# brakelight_V3.net
KiCad netlist of a schematic drawn in EAGLE
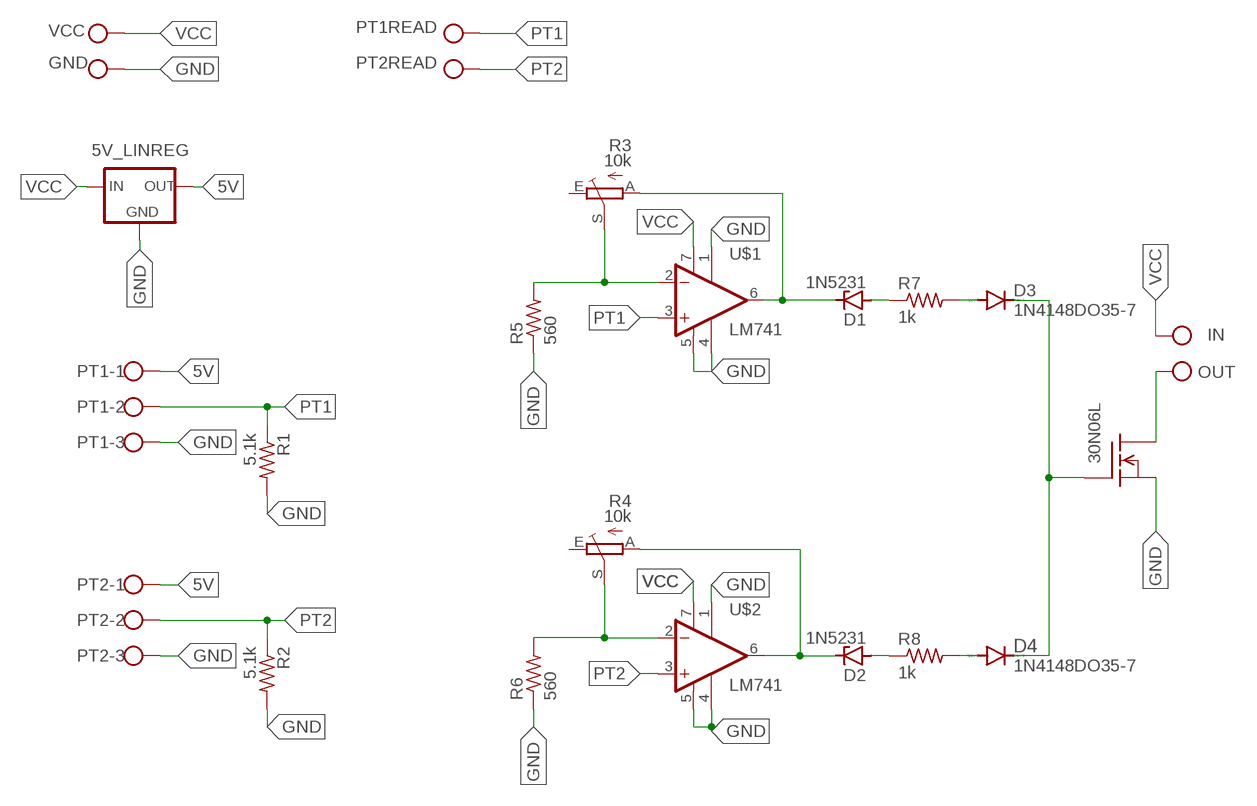
[diagram p0: schematic, sheet 1]

(export (version "E")
  (design (tool "Eeschema 10.0.6"))
  (components
    (comp (ref "5V_LINREG")
      (value "78XXL")
      (footprint "eagle-import:78XXL")
      (libsource (lib "eagle-import") (part "78XXL"))
    )
    (comp (ref "BRAKELIGHT")
      (value "W237-102")
      (footprint "eagle-import:W237-102")
      (fields (field (name "MPN") "237-102"))
      (libsource (lib "eagle-import") (part "W237-102"))
    )
    (comp (ref "D1")
      (value "1N5231")
      (footprint "eagle-import:DO34Z7")
      (libsource (lib "eagle-import") (part "ZENER-DIODEDO34-7"))
    )
    (comp (ref "D2")
      (value "1N5231")
      (footprint "eagle-import:DO34Z7")
      (libsource (lib "eagle-import") (part "ZENER-DIODEDO34-7"))
    )
    (comp (ref "D3")
      (value "1N4148DO35-7")
      (footprint "eagle-import:DO35-7")
      (libsource (lib "eagle-import") (part "1N4148DO35-7"))
    )
    (comp (ref "D4")
      (value "1N4148DO35-7")
      (footprint "eagle-import:DO35-7")
      (libsource (lib "eagle-import") (part "1N4148DO35-7"))
    )
    (comp (ref "INO_READ")
      (value "W237-102")
      (footprint "eagle-import:W237-102")
      (fields (field (name "MPN") "237-102"))
      (libsource (lib "eagle-import") (part "W237-102"))
    )
    (comp (ref "LIPO_CONN")
      (value "W237-102")
      (footprint "eagle-import:W237-102")
      (fields (field (name "MPN") "237-102"))
      (libsource (lib "eagle-import") (part "W237-102"))
    )
    (comp (ref "PT1")
      (value "W237-103")
      (footprint "eagle-import:W237-103")
      (fields (field (name "MPN") "237-103"))
      (libsource (lib "eagle-import") (part "W237-103"))
    )
    (comp (ref "PT2")
      (value "W237-103")
      (footprint "eagle-import:W237-103")
      (fields (field (name "MPN") "237-103"))
      (libsource (lib "eagle-import") (part "W237-103"))
    )
    (comp (ref "Q2")
      (value "30N06L")
      (footprint "eagle-import:TO220")
      (fields (field (name "SPICEPREFIX") "Q"))
      (libsource (lib "eagle-import") (part "SUP75N06-08"))
    )
    (comp (ref "R1")
      (value "5.1k")
      (footprint "eagle-import:0207_5V")
      (libsource (lib "eagle-import") (part "R-US_0207/5V"))
    )
    (comp (ref "R2")
      (value "5.1k")
      (footprint "eagle-import:0207_5V")
      (libsource (lib "eagle-import") (part "R-US_0207/5V"))
    )
    (comp (ref "R3")
      (value "10k")
      (footprint "eagle-import:RS3")
      (libsource (lib "eagle-import") (part "TRIM_EU-RS3"))
    )
    (comp (ref "R4")
      (value "10k")
      (footprint "eagle-import:RS3")
      (libsource (lib "eagle-import") (part "TRIM_EU-RS3"))
    )
    (comp (ref "R5")
      (value "560")
      (footprint "eagle-import:0207_5V")
      (libsource (lib "eagle-import") (part "R-US_0207/5V"))
    )
    (comp (ref "R6")
      (value "560")
      (footprint "eagle-import:0207_5V")
      (libsource (lib "eagle-import") (part "R-US_0207/5V"))
    )
    (comp (ref "R7")
      (value "1k")
      (footprint "eagle-import:0204_5")
      (libsource (lib "eagle-import") (part "R-US_0204/5"))
    )
    (comp (ref "R8")
      (value "1k")
      (footprint "eagle-import:0204_5")
      (libsource (lib "eagle-import") (part "R-US_0204/5"))
    )
    (comp (ref "U$1")
      (value "LM741")
      (footprint "eagle-import:DIL08")
      (libsource (lib "eagle-import") (part "LM741"))
    )
    (comp (ref "U$2")
      (value "LM741")
      (footprint "eagle-import:DIL08")
      (fields (field (name "SPICEPREFIX") "X"))
      (libsource (lib "eagle-import") (part "LM741"))
    )
  )
  (nets
    (net (code "1") (name "5V") (class "Default")
      (node (ref "5V_LINREG") (pin "OUT") (pinfunction "OUT_OUT") (pintype "passive"))
      (node (ref "PT1") (pin "1") (pinfunction "KL_1") (pintype "passive"))
      (node (ref "PT2") (pin "1") (pinfunction "KL_1") (pintype "passive"))
    )
    (net (code "2") (name "GND") (class "Default")
      (node (ref "5V_LINREG") (pin "GND") (pinfunction "GND_GND") (pintype "input"))
      (node (ref "LIPO_CONN") (pin "2") (pinfunction "KL_2") (pintype "passive"))
      (node (ref "PT1") (pin "3") (pinfunction "KL_3") (pintype "passive"))
      (node (ref "PT2") (pin "3") (pinfunction "KL_3") (pintype "passive"))
      (node (ref "Q2") (pin "3") (pinfunction "S_3") (pintype "passive"))
      (node (ref "R1") (pin "2") (pinfunction "2_2") (pintype "passive"))
      (node (ref "R2") (pin "2") (pinfunction "2_2") (pintype "passive"))
      (node (ref "R5") (pin "1") (pinfunction "1_1") (pintype "passive"))
      (node (ref "R6") (pin "1") (pinfunction "1_1") (pintype "passive"))
      (node (ref "U$1") (pin "1") (pinfunction "OFFSETNULL_1") (pintype "bidirectional"))
      (node (ref "U$1") (pin "4") (pinfunction "V-_4") (pintype "passive"))
      (node (ref "U$1") (pin "5") (pinfunction "OFFSETNULL2_5") (pintype "bidirectional"))
      (node (ref "U$2") (pin "1") (pinfunction "OFFSETNULL_1") (pintype "bidirectional"))
      (node (ref "U$2") (pin "4") (pinfunction "V-_4") (pintype "passive"))
      (node (ref "U$2") (pin "5") (pinfunction "OFFSETNULL2_5") (pintype "bidirectional"))
    )
    (net (code "3") (name "Net-(BRAKELIGHTB-KL)") (class "Default")
      (node (ref "BRAKELIGHT") (pin "2") (pinfunction "KL_2") (pintype "passive"))
      (node (ref "Q2") (pin "2") (pinfunction "D_2") (pintype "passive"))
    )
    (net (code "4") (name "Net-(D1-PadA)") (class "Default")
      (node (ref "D1") (pin "A") (pinfunction "A_A") (pintype "passive"))
      (node (ref "R7") (pin "1") (pinfunction "1_1") (pintype "passive"))
    )
    (net (code "5") (name "Net-(D2-PadA)") (class "Default")
      (node (ref "D2") (pin "A") (pinfunction "A_A") (pintype "passive"))
      (node (ref "R8") (pin "1") (pinfunction "1_1") (pintype "passive"))
    )
    (net (code "6") (name "Net-(D3-PadA)") (class "Default")
      (node (ref "D3") (pin "A") (pinfunction "A_A") (pintype "passive"))
      (node (ref "R7") (pin "2") (pinfunction "2_2") (pintype "passive"))
    )
    (net (code "7") (name "Net-(D4-PadA)") (class "Default")
      (node (ref "D4") (pin "A") (pinfunction "A_A") (pintype "passive"))
      (node (ref "R8") (pin "2") (pinfunction "2_2") (pintype "passive"))
    )
    (net (code "8") (name "Net-(Q2-G)") (class "Default")
      (node (ref "D3") (pin "C") (pinfunction "C_C") (pintype "passive"))
      (node (ref "D4") (pin "C") (pinfunction "C_C") (pintype "passive"))
      (node (ref "Q2") (pin "1") (pinfunction "G_1") (pintype "passive"))
    )
    (net (code "9") (name "Net-(U$1-INV_INPUT)") (class "Default")
      (node (ref "R3") (pin "S") (pinfunction "S_S") (pintype "passive"))
      (node (ref "R5") (pin "2") (pinfunction "2_2") (pintype "passive"))
      (node (ref "U$1") (pin "2") (pinfunction "INV_INPUT_2") (pintype "input"))
    )
    (net (code "10") (name "Net-(U$1-OUT)") (class "Default")
      (node (ref "D1") (pin "C") (pinfunction "C_C") (pintype "passive"))
      (node (ref "R3") (pin "A") (pinfunction "A_A") (pintype "passive"))
      (node (ref "U$1") (pin "6") (pinfunction "OUT_6") (pintype "output"))
    )
    (net (code "11") (name "Net-(U$2-INV_INPUT)") (class "Default")
      (node (ref "R4") (pin "S") (pinfunction "S_S") (pintype "passive"))
      (node (ref "R6") (pin "2") (pinfunction "2_2") (pintype "passive"))
      (node (ref "U$2") (pin "2") (pinfunction "INV_INPUT_2") (pintype "input"))
    )
    (net (code "12") (name "Net-(U$2-OUT)") (class "Default")
      (node (ref "D2") (pin "C") (pinfunction "C_C") (pintype "passive"))
      (node (ref "R4") (pin "A") (pinfunction "A_A") (pintype "passive"))
      (node (ref "U$2") (pin "6") (pinfunction "OUT_6") (pintype "output"))
    )
    (net (code "13") (name "PT1") (class "Default")
      (node (ref "INO_READ") (pin "1") (pinfunction "KL_1") (pintype "passive"))
      (node (ref "PT1") (pin "2") (pinfunction "KL_2") (pintype "passive"))
      (node (ref "R1") (pin "1") (pinfunction "1_1") (pintype "passive"))
      (node (ref "U$1") (pin "3") (pinfunction "NONINV_INPUT_3") (pintype "input"))
    )
    (net (code "14") (name "PT2") (class "Default")
      (node (ref "INO_READ") (pin "2") (pinfunction "KL_2") (pintype "passive"))
      (node (ref "PT2") (pin "2") (pinfunction "KL_2") (pintype "passive"))
      (node (ref "R2") (pin "1") (pinfunction "1_1") (pintype "passive"))
      (node (ref "U$2") (pin "3") (pinfunction "NONINV_INPUT_3") (pintype "input"))
    )
    (net (code "15") (name "VCC") (class "Default")
      (node (ref "5V_LINREG") (pin "IN") (pinfunction "IN_IN") (pintype "input"))
      (node (ref "BRAKELIGHT") (pin "1") (pinfunction "KL_1") (pintype "passive"))
      (node (ref "LIPO_CONN") (pin "1") (pinfunction "KL_1") (pintype "passive"))
      (node (ref "U$1") (pin "7") (pinfunction "V+_7") (pintype "power_in"))
      (node (ref "U$2") (pin "7") (pinfunction "V+_7") (pintype "power_in"))
    )
    (net (code "16") (name "unconnected-(R3-PadE)") (class "Default")
      (node (ref "R3") (pin "E") (pinfunction "E_E") (pintype "passive"))
    )
    (net (code "17") (name "unconnected-(R4-PadE)") (class "Default")
      (node (ref "R4") (pin "E") (pinfunction "E_E") (pintype "passive"))
    )
  )
)
